# Motor_Surucu_V2.net
KiCad netlist of a schematic drawn in EAGLE
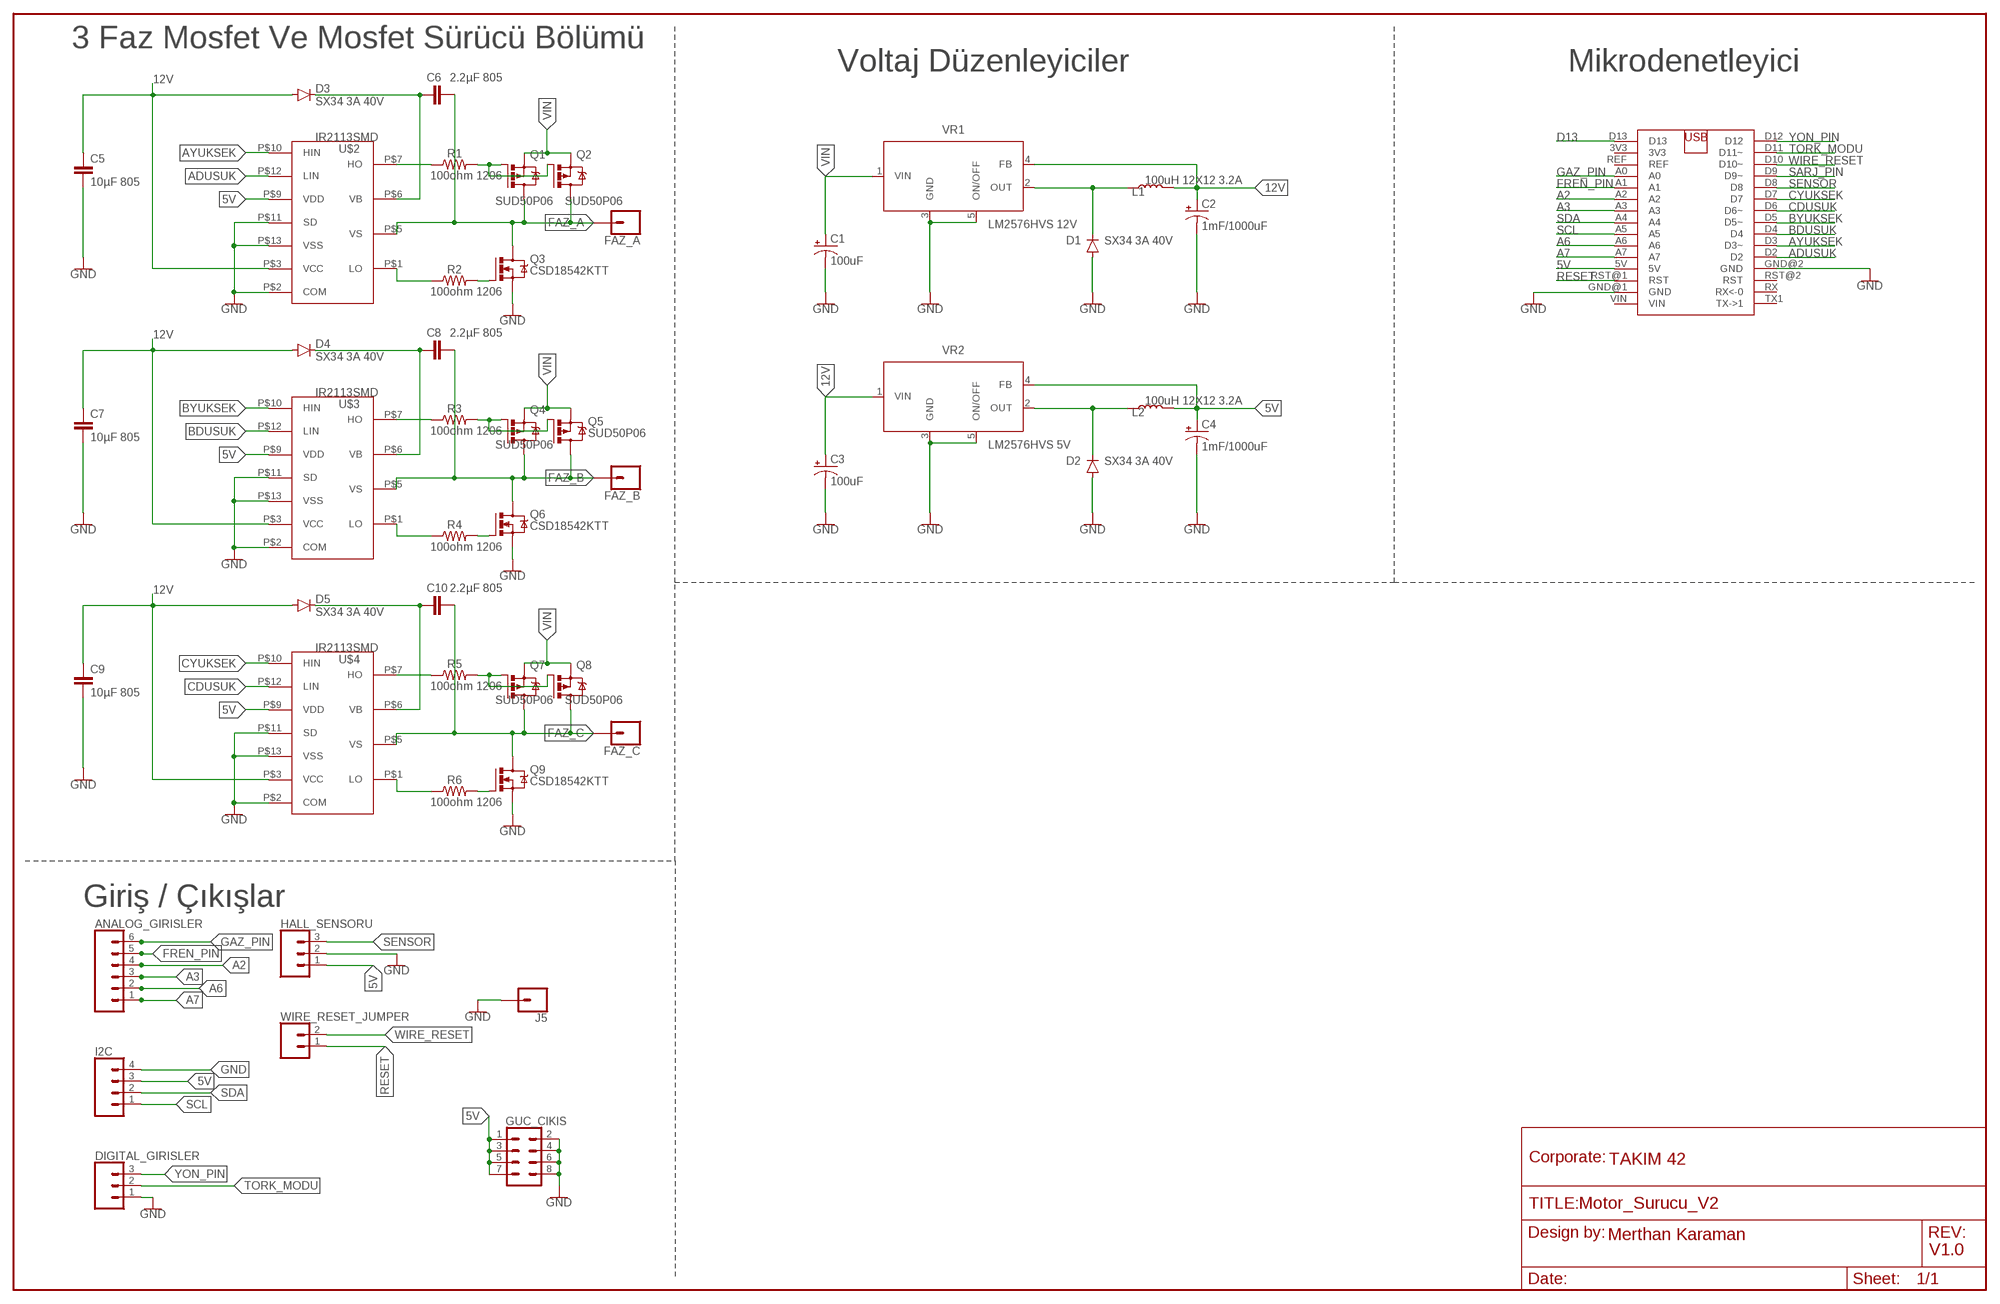
[diagram p0: schematic, sheet 1]

(export (version "E")
  (design (tool "Eeschema 10.0.6"))
  (components
    (comp (ref "ANALOG_GIRISLER")
      (value "CONN_06SILK_FEMALE_PTH")
      (footprint "eagle-import:1X06")
      (libsource (lib "eagle-import") (part "CONN_06SILK_FEMALE_PTH"))
    )
    (comp (ref "C1")
      (value "100uF")
      (footprint "eagle-import:CPOL-RADIAL-2.5MM-6.5MM")
      (libsource (lib "eagle-import") (part "100UF-POLAR-RADIAL-2.5MM-25V-20%"))
    )
    (comp (ref "C2")
      (value "1mF/1000uF")
      (footprint "eagle-import:PANASONIC_G")
      (libsource (lib "eagle-import") (part "560UF-PANASONIC_G-25V-20%"))
    )
    (comp (ref "C3")
      (value "100uF")
      (footprint "eagle-import:CPOL-RADIAL-2.5MM-6.5MM")
      (libsource (lib "eagle-import") (part "100UF-POLAR-RADIAL-2.5MM-25V-20%"))
    )
    (comp (ref "C4")
      (value "1mF/1000uF")
      (footprint "eagle-import:PANASONIC_G")
      (libsource (lib "eagle-import") (part "560UF-PANASONIC_G-25V-20%"))
    )
    (comp (ref "C5")
      (value "10µF 805")
      (footprint "eagle-import:0805")
      (libsource (lib "eagle-import") (part "0.33UF/330NF-0805-50V-10%"))
    )
    (comp (ref "C6")
      (value "2.2µF 805")
      (footprint "eagle-import:0805")
      (libsource (lib "eagle-import") (part "0.33UF/330NF-0805-50V-10%"))
    )
    (comp (ref "C7")
      (value "10µF 805")
      (footprint "eagle-import:0805")
      (libsource (lib "eagle-import") (part "0.33UF/330NF-0805-50V-10%"))
    )
    (comp (ref "C8")
      (value "2.2µF 805")
      (footprint "eagle-import:0805")
      (libsource (lib "eagle-import") (part "0.33UF/330NF-0805-50V-10%"))
    )
    (comp (ref "C9")
      (value "10µF 805")
      (footprint "eagle-import:0805")
      (libsource (lib "eagle-import") (part "0.33UF/330NF-0805-50V-10%"))
    )
    (comp (ref "C10")
      (value "2.2µF 805")
      (footprint "eagle-import:0805")
      (libsource (lib "eagle-import") (part "0.33UF/330NF-0805-50V-10%"))
    )
    (comp (ref "D1")
      (value "SX34 3A 40V")
      (footprint "eagle-import:DO214AC")
      (libsource (lib "eagle-import") (part "DIODE-DO214AC"))
    )
    (comp (ref "D2")
      (value "SX34 3A 40V")
      (footprint "eagle-import:DO214AC")
      (libsource (lib "eagle-import") (part "DIODE-DO214AC"))
    )
    (comp (ref "D3")
      (value "SX34 3A 40V")
      (footprint "eagle-import:DO214AC")
      (libsource (lib "eagle-import") (part "DIODE-DO214AC"))
    )
    (comp (ref "D4")
      (value "SX34 3A 40V")
      (footprint "eagle-import:DO214AC")
      (libsource (lib "eagle-import") (part "DIODE-DO214AC"))
    )
    (comp (ref "D5")
      (value "SX34 3A 40V")
      (footprint "eagle-import:DO214AC")
      (libsource (lib "eagle-import") (part "DIODE-DO214AC"))
    )
    (comp (ref "DIGITAL_GIRISLER")
      (value "CONN_03")
      (footprint "eagle-import:1X03")
      (libsource (lib "eagle-import") (part "CONN_03"))
    )
    (comp (ref "FAZ_A")
      (value "CONN_01SNAP-MALE")
      (footprint "eagle-import:SNAP-MALE")
      (libsource (lib "eagle-import") (part "CONN_01SNAP-MALE"))
    )
    (comp (ref "FAZ_B")
      (value "CONN_01SNAP-MALE")
      (footprint "eagle-import:SNAP-MALE")
      (libsource (lib "eagle-import") (part "CONN_01SNAP-MALE"))
    )
    (comp (ref "FAZ_C")
      (value "CONN_01SNAP-MALE")
      (footprint "eagle-import:SNAP-MALE")
      (libsource (lib "eagle-import") (part "CONN_01SNAP-MALE"))
    )
    (comp (ref "GUC_CIKIS")
      (value "CONN_04X2")
      (footprint "eagle-import:2X4")
      (libsource (lib "eagle-import") (part "CONN_04X2"))
    )
    (comp (ref "HALL_SENSORU")
      (value "CONN_03")
      (footprint "eagle-import:1X03")
      (libsource (lib "eagle-import") (part "CONN_03"))
    )
    (comp (ref "I2C")
      (value "CONN_04")
      (footprint "eagle-import:1X04")
      (libsource (lib "eagle-import") (part "CONN_04"))
    )
    (comp (ref "J5")
      (value "CONN_01SNAP-MALE")
      (footprint "eagle-import:SNAP-MALE")
      (libsource (lib "eagle-import") (part "CONN_01SNAP-MALE"))
    )
    (comp (ref "L1")
      (value "100uH 12X12 3.2A")
      (footprint "eagle-import:INDUCTOR_SDR1307")
      (libsource (lib "eagle-import") (part "INDUCTOR-SDR13-27UH"))
    )
    (comp (ref "L2")
      (value "100uH 12X12 3.2A")
      (footprint "eagle-import:INDUCTOR_SDR1307")
      (libsource (lib "eagle-import") (part "INDUCTOR-SDR13-27UH"))
    )
    (comp (ref "Q1")
      (value "SUD50P06")
      (footprint "eagle-import:TO-252")
      (libsource (lib "eagle-import") (part "SUD50P06"))
    )
    (comp (ref "Q2")
      (value "SUD50P06")
      (footprint "eagle-import:TO-252")
      (libsource (lib "eagle-import") (part "SUD50P06"))
    )
    (comp (ref "Q3")
      (value "CSD18542KTT")
      (footprint "eagle-import:TO263-3")
      (libsource (lib "eagle-import") (part "CSD18542KTT"))
    )
    (comp (ref "Q4")
      (value "SUD50P06")
      (footprint "eagle-import:TO-252")
      (libsource (lib "eagle-import") (part "SUD50P06"))
    )
    (comp (ref "Q5")
      (value "SUD50P06")
      (footprint "eagle-import:TO-252")
      (libsource (lib "eagle-import") (part "SUD50P06"))
    )
    (comp (ref "Q6")
      (value "CSD18542KTT")
      (footprint "eagle-import:TO263-3")
      (libsource (lib "eagle-import") (part "CSD18542KTT"))
    )
    (comp (ref "Q7")
      (value "SUD50P06")
      (footprint "eagle-import:TO-252")
      (libsource (lib "eagle-import") (part "SUD50P06"))
    )
    (comp (ref "Q8")
      (value "SUD50P06")
      (footprint "eagle-import:TO-252")
      (libsource (lib "eagle-import") (part "SUD50P06"))
    )
    (comp (ref "Q9")
      (value "CSD18542KTT")
      (footprint "eagle-import:TO263-3")
      (libsource (lib "eagle-import") (part "CSD18542KTT"))
    )
    (comp (ref "R1")
      (value "100ohm 1206")
      (footprint "eagle-import:1206")
      (libsource (lib "eagle-import") (part "RESISTOR1206"))
    )
    (comp (ref "R2")
      (value "100ohm 1206")
      (footprint "eagle-import:1206")
      (libsource (lib "eagle-import") (part "RESISTOR1206"))
    )
    (comp (ref "R3")
      (value "100ohm 1206")
      (footprint "eagle-import:1206")
      (libsource (lib "eagle-import") (part "RESISTOR1206"))
    )
    (comp (ref "R4")
      (value "100ohm 1206")
      (footprint "eagle-import:1206")
      (libsource (lib "eagle-import") (part "RESISTOR1206"))
    )
    (comp (ref "R5")
      (value "100ohm 1206")
      (footprint "eagle-import:1206")
      (libsource (lib "eagle-import") (part "RESISTOR1206"))
    )
    (comp (ref "R6")
      (value "100ohm 1206")
      (footprint "eagle-import:1206")
      (libsource (lib "eagle-import") (part "RESISTOR1206"))
    )
    (comp (ref "U$1")
      (value "ARDUINO_NANO")
      (footprint "eagle-import:ARDUINO_NANO")
      (libsource (lib "eagle-import") (part "ARDUINO_NANO"))
    )
    (comp (ref "U$2")
      (value "IR2113SMD")
      (footprint "eagle-import:SOIC-14")
      (libsource (lib "eagle-import") (part "IR2113SMD"))
    )
    (comp (ref "U$3")
      (value "IR2113SMD")
      (footprint "eagle-import:SOIC-14")
      (libsource (lib "eagle-import") (part "IR2113SMD"))
    )
    (comp (ref "U$4")
      (value "IR2113SMD")
      (footprint "eagle-import:SOIC-14")
      (libsource (lib "eagle-import") (part "IR2113SMD"))
    )
    (comp (ref "VR1")
      (value "LM2576HVS 12V")
      (footprint "eagle-import:TO170P1435X465-6N")
      (fields (field (name "MANUFACTURER") "TI") (field (name "MPN") "LM2576HVS-5.0/NOPB"))
      (libsource (lib "eagle-import") (part "LM2576HVS-5.0/NOPBTO-263"))
    )
    (comp (ref "VR2")
      (value "LM2576HVS 5V")
      (footprint "eagle-import:TO170P1435X465-6N")
      (fields (field (name "MANUFACTURER") "TI") (field (name "MPN") "LM2576HVS-5.0/NOPB"))
      (libsource (lib "eagle-import") (part "LM2576HVS-5.0/NOPBTO-263"))
    )
    (comp (ref "WIRE_RESET_JUMPER")
      (value "CONN_02")
      (footprint "eagle-import:1X02")
      (libsource (lib "eagle-import") (part "CONN_02"))
    )
  )
  (nets
    (net (code "1") (name "/D13") (class "Default")
      (node (ref "U$1") (pin "D13") (pinfunction "D13_D13") (pintype "bidirectional"))
    )
    (net (code "2") (name "/SARJ_PIN") (class "Default")
      (node (ref "U$1") (pin "D9") (pinfunction "D9~{}_D9") (pintype "bidirectional"))
    )
    (net (code "3") (name "5V") (class "Default")
      (node (ref "C4") (pin "+") (pinfunction "+_+") (pintype "passive"))
      (node (ref "GUC_CIKIS") (pin "1") (pinfunction "1_1") (pintype "passive"))
      (node (ref "GUC_CIKIS") (pin "3") (pinfunction "3_3") (pintype "passive"))
      (node (ref "GUC_CIKIS") (pin "5") (pinfunction "5_5") (pintype "passive"))
      (node (ref "GUC_CIKIS") (pin "7") (pinfunction "7_7") (pintype "passive"))
      (node (ref "HALL_SENSORU") (pin "1") (pinfunction "1_1") (pintype "passive"))
      (node (ref "I2C") (pin "3") (pinfunction "3_3") (pintype "passive"))
      (node (ref "L2") (pin "P$2") (pinfunction "2_P$2") (pintype "passive"))
      (node (ref "U$1") (pin "5V") (pinfunction "5V_5V") (pintype "bidirectional"))
      (node (ref "U$2") (pin "P$9") (pinfunction "VDD_P$9") (pintype "bidirectional"))
      (node (ref "U$3") (pin "P$9") (pinfunction "VDD_P$9") (pintype "bidirectional"))
      (node (ref "U$4") (pin "P$9") (pinfunction "VDD_P$9") (pintype "bidirectional"))
      (node (ref "VR2") (pin "4") (pinfunction "FB_4") (pintype "output"))
    )
    (net (code "4") (name "12V") (class "Default")
      (node (ref "C2") (pin "+") (pinfunction "+_+") (pintype "passive"))
      (node (ref "C3") (pin "1") (pinfunction "+_1") (pintype "passive"))
      (node (ref "C5") (pin "1") (pinfunction "1_1") (pintype "passive"))
      (node (ref "C7") (pin "1") (pinfunction "1_1") (pintype "passive"))
      (node (ref "C9") (pin "1") (pinfunction "1_1") (pintype "passive"))
      (node (ref "D3") (pin "A") (pinfunction "A_A") (pintype "passive"))
      (node (ref "D4") (pin "A") (pinfunction "A_A") (pintype "passive"))
      (node (ref "D5") (pin "A") (pinfunction "A_A") (pintype "passive"))
      (node (ref "L1") (pin "P$2") (pinfunction "2_P$2") (pintype "passive"))
      (node (ref "U$2") (pin "P$3") (pinfunction "VCC_P$3") (pintype "bidirectional"))
      (node (ref "U$3") (pin "P$3") (pinfunction "VCC_P$3") (pintype "bidirectional"))
      (node (ref "U$4") (pin "P$3") (pinfunction "VCC_P$3") (pintype "bidirectional"))
      (node (ref "VR1") (pin "4") (pinfunction "FB_4") (pintype "output"))
      (node (ref "VR2") (pin "1") (pinfunction "VIN_1") (pintype "input"))
    )
    (net (code "5") (name "A2") (class "Default")
      (node (ref "ANALOG_GIRISLER") (pin "4") (pinfunction "4_4") (pintype "passive"))
      (node (ref "U$1") (pin "A2") (pinfunction "A2_A2") (pintype "bidirectional"))
    )
    (net (code "6") (name "A3") (class "Default")
      (node (ref "ANALOG_GIRISLER") (pin "3") (pinfunction "3_3") (pintype "passive"))
      (node (ref "U$1") (pin "A3") (pinfunction "A3_A3") (pintype "bidirectional"))
    )
    (net (code "7") (name "A6") (class "Default")
      (node (ref "ANALOG_GIRISLER") (pin "2") (pinfunction "2_2") (pintype "passive"))
      (node (ref "U$1") (pin "A6") (pinfunction "A6_A6") (pintype "bidirectional"))
    )
    (net (code "8") (name "A7") (class "Default")
      (node (ref "ANALOG_GIRISLER") (pin "1") (pinfunction "1_1") (pintype "passive"))
      (node (ref "U$1") (pin "A7") (pinfunction "A7_A7") (pintype "bidirectional"))
    )
    (net (code "9") (name "ADUSUK") (class "Default")
      (node (ref "U$1") (pin "D2") (pinfunction "D2_D2") (pintype "bidirectional"))
      (node (ref "U$2") (pin "P$12") (pinfunction "LIN_P$12") (pintype "bidirectional"))
    )
    (net (code "10") (name "AYUKSEK") (class "Default")
      (node (ref "U$1") (pin "D3") (pinfunction "D3~{}_D3") (pintype "bidirectional"))
      (node (ref "U$2") (pin "P$10") (pinfunction "HIN_P$10") (pintype "bidirectional"))
    )
    (net (code "11") (name "BDUSUK") (class "Default")
      (node (ref "U$1") (pin "D4") (pinfunction "D4_D4") (pintype "bidirectional"))
      (node (ref "U$3") (pin "P$12") (pinfunction "LIN_P$12") (pintype "bidirectional"))
    )
    (net (code "12") (name "BYUKSEK") (class "Default")
      (node (ref "U$1") (pin "D5") (pinfunction "D5~{}_D5") (pintype "bidirectional"))
      (node (ref "U$3") (pin "P$10") (pinfunction "HIN_P$10") (pintype "bidirectional"))
    )
    (net (code "13") (name "CDUSUK") (class "Default")
      (node (ref "U$1") (pin "D6") (pinfunction "D6~{}_D6") (pintype "bidirectional"))
      (node (ref "U$4") (pin "P$12") (pinfunction "LIN_P$12") (pintype "bidirectional"))
    )
    (net (code "14") (name "CYUKSEK") (class "Default")
      (node (ref "U$1") (pin "D7") (pinfunction "D7_D7") (pintype "bidirectional"))
      (node (ref "U$4") (pin "P$10") (pinfunction "HIN_P$10") (pintype "bidirectional"))
    )
    (net (code "15") (name "FAZ_A") (class "Default")
      (node (ref "C6") (pin "2") (pinfunction "2_2") (pintype "passive"))
      (node (ref "FAZ_A") (pin "2") (pinfunction "1_2") (pintype "passive"))
      (node (ref "Q1") (pin "TAB") (pinfunction "D_TAB") (pintype "passive"))
      (node (ref "Q2") (pin "TAB") (pinfunction "D_TAB") (pintype "passive"))
      (node (ref "Q3") (pin "TAB") (pinfunction "D_TAB") (pintype "passive"))
      (node (ref "U$2") (pin "P$5") (pinfunction "VS_P$5") (pintype "bidirectional"))
    )
    (net (code "16") (name "FAZ_B") (class "Default")
      (node (ref "C8") (pin "2") (pinfunction "2_2") (pintype "passive"))
      (node (ref "FAZ_B") (pin "2") (pinfunction "1_2") (pintype "passive"))
      (node (ref "Q4") (pin "TAB") (pinfunction "D_TAB") (pintype "passive"))
      (node (ref "Q5") (pin "TAB") (pinfunction "D_TAB") (pintype "passive"))
      (node (ref "Q6") (pin "TAB") (pinfunction "D_TAB") (pintype "passive"))
      (node (ref "U$3") (pin "P$5") (pinfunction "VS_P$5") (pintype "bidirectional"))
    )
    (net (code "17") (name "FAZ_C") (class "Default")
      (node (ref "C10") (pin "2") (pinfunction "2_2") (pintype "passive"))
      (node (ref "FAZ_C") (pin "2") (pinfunction "1_2") (pintype "passive"))
      (node (ref "Q7") (pin "TAB") (pinfunction "D_TAB") (pintype "passive"))
      (node (ref "Q8") (pin "TAB") (pinfunction "D_TAB") (pintype "passive"))
      (node (ref "Q9") (pin "TAB") (pinfunction "D_TAB") (pintype "passive"))
      (node (ref "U$4") (pin "P$5") (pinfunction "VS_P$5") (pintype "bidirectional"))
    )
    (net (code "18") (name "FREN_PIN") (class "Default")
      (node (ref "ANALOG_GIRISLER") (pin "5") (pinfunction "5_5") (pintype "passive"))
      (node (ref "U$1") (pin "A1") (pinfunction "A1_A1") (pintype "bidirectional"))
    )
    (net (code "19") (name "GAZ_PIN") (class "Default")
      (node (ref "ANALOG_GIRISLER") (pin "6") (pinfunction "6_6") (pintype "passive"))
      (node (ref "U$1") (pin "A0") (pinfunction "A0_A0") (pintype "bidirectional"))
    )
    (net (code "20") (name "GND") (class "Default")
      (node (ref "C1") (pin "2") (pinfunction "-_2") (pintype "passive"))
      (node (ref "C2") (pin "-") (pinfunction "-_-") (pintype "passive"))
      (node (ref "C3") (pin "2") (pinfunction "-_2") (pintype "passive"))
      (node (ref "C4") (pin "-") (pinfunction "-_-") (pintype "passive"))
      (node (ref "C5") (pin "2") (pinfunction "2_2") (pintype "passive"))
      (node (ref "C7") (pin "2") (pinfunction "2_2") (pintype "passive"))
      (node (ref "C9") (pin "2") (pinfunction "2_2") (pintype "passive"))
      (node (ref "D1") (pin "A") (pinfunction "A_A") (pintype "passive"))
      (node (ref "D2") (pin "A") (pinfunction "A_A") (pintype "passive"))
      (node (ref "DIGITAL_GIRISLER") (pin "1") (pinfunction "1_1") (pintype "passive"))
      (node (ref "GUC_CIKIS") (pin "2") (pinfunction "2_2") (pintype "passive"))
      (node (ref "GUC_CIKIS") (pin "4") (pinfunction "4_4") (pintype "passive"))
      (node (ref "GUC_CIKIS") (pin "6") (pinfunction "6_6") (pintype "passive"))
      (node (ref "GUC_CIKIS") (pin "8") (pinfunction "8_8") (pintype "passive"))
      (node (ref "HALL_SENSORU") (pin "2") (pinfunction "2_2") (pintype "passive"))
      (node (ref "I2C") (pin "4") (pinfunction "4_4") (pintype "passive"))
      (node (ref "J5") (pin "2") (pinfunction "1_2") (pintype "passive"))
      (node (ref "Q3") (pin "3") (pinfunction "S_3") (pintype "passive"))
      (node (ref "Q6") (pin "3") (pinfunction "S_3") (pintype "passive"))
      (node (ref "Q9") (pin "3") (pinfunction "S_3") (pintype "passive"))
      (node (ref "U$1") (pin "GND@1") (pinfunction "GND_GND@1") (pintype "bidirectional"))
      (node (ref "U$1") (pin "GND@2") (pinfunction "GND_GND@2") (pintype "bidirectional"))
      (node (ref "U$2") (pin "P$11") (pinfunction "SD_P$11") (pintype "bidirectional"))
      (node (ref "U$2") (pin "P$13") (pinfunction "VSS_P$13") (pintype "bidirectional"))
      (node (ref "U$2") (pin "P$2") (pinfunction "COM_P$2") (pintype "bidirectional"))
      (node (ref "U$3") (pin "P$11") (pinfunction "SD_P$11") (pintype "bidirectional"))
      (node (ref "U$3") (pin "P$13") (pinfunction "VSS_P$13") (pintype "bidirectional"))
      (node (ref "U$3") (pin "P$2") (pinfunction "COM_P$2") (pintype "bidirectional"))
      (node (ref "U$4") (pin "P$11") (pinfunction "SD_P$11") (pintype "bidirectional"))
      (node (ref "U$4") (pin "P$13") (pinfunction "VSS_P$13") (pintype "bidirectional"))
      (node (ref "U$4") (pin "P$2") (pinfunction "COM_P$2") (pintype "bidirectional"))
      (node (ref "VR1") (pin "3") (pinfunction "GND_3") (pintype "passive"))
      (node (ref "VR1") (pin "5") (pinfunction "ON/OFF_5") (pintype "input"))
      (node (ref "VR2") (pin "3") (pinfunction "GND_3") (pintype "passive"))
      (node (ref "VR2") (pin "5") (pinfunction "ON/OFF_5") (pintype "input"))
    )
    (net (code "21") (name "Net-(L1-1)") (class "Default")
      (node (ref "D1") (pin "C") (pinfunction "C_C") (pintype "passive"))
      (node (ref "L1") (pin "P$1") (pinfunction "1_P$1") (pintype "passive"))
      (node (ref "VR1") (pin "2") (pinfunction "OUT_2") (pintype "output"))
    )
    (net (code "22") (name "Net-(L2-1)") (class "Default")
      (node (ref "D2") (pin "C") (pinfunction "C_C") (pintype "passive"))
      (node (ref "L2") (pin "P$1") (pinfunction "1_P$1") (pintype "passive"))
      (node (ref "VR2") (pin "2") (pinfunction "OUT_2") (pintype "output"))
    )
    (net (code "23") (name "Net-(Q1-G)") (class "Default")
      (node (ref "Q1") (pin "1") (pinfunction "G_1") (pintype "passive"))
      (node (ref "Q2") (pin "1") (pinfunction "G_1") (pintype "passive"))
      (node (ref "R1") (pin "2") (pinfunction "2_2") (pintype "passive"))
    )
    (net (code "24") (name "Net-(Q3-G)") (class "Default")
      (node (ref "Q3") (pin "1") (pinfunction "G_1") (pintype "passive"))
      (node (ref "R2") (pin "2") (pinfunction "2_2") (pintype "passive"))
    )
    (net (code "25") (name "Net-(Q4-G)") (class "Default")
      (node (ref "Q4") (pin "1") (pinfunction "G_1") (pintype "passive"))
      (node (ref "Q5") (pin "1") (pinfunction "G_1") (pintype "passive"))
      (node (ref "R3") (pin "2") (pinfunction "2_2") (pintype "passive"))
    )
    (net (code "26") (name "Net-(Q6-G)") (class "Default")
      (node (ref "Q6") (pin "1") (pinfunction "G_1") (pintype "passive"))
      (node (ref "R4") (pin "2") (pinfunction "2_2") (pintype "passive"))
    )
    (net (code "27") (name "Net-(Q7-G)") (class "Default")
      (node (ref "Q7") (pin "1") (pinfunction "G_1") (pintype "passive"))
      (node (ref "Q8") (pin "1") (pinfunction "G_1") (pintype "passive"))
      (node (ref "R5") (pin "2") (pinfunction "2_2") (pintype "passive"))
    )
    (net (code "28") (name "Net-(Q9-G)") (class "Default")
      (node (ref "Q9") (pin "1") (pinfunction "G_1") (pintype "passive"))
      (node (ref "R6") (pin "2") (pinfunction "2_2") (pintype "passive"))
    )
    (net (code "29") (name "Net-(U$2-HO)") (class "Default")
      (node (ref "R1") (pin "1") (pinfunction "1_1") (pintype "passive"))
      (node (ref "U$2") (pin "P$7") (pinfunction "HO_P$7") (pintype "bidirectional"))
    )
    (net (code "30") (name "Net-(U$2-LO)") (class "Default")
      (node (ref "R2") (pin "1") (pinfunction "1_1") (pintype "passive"))
      (node (ref "U$2") (pin "P$1") (pinfunction "LO_P$1") (pintype "bidirectional"))
    )
    (net (code "31") (name "Net-(U$2-VB)") (class "Default")
      (node (ref "C6") (pin "1") (pinfunction "1_1") (pintype "passive"))
      (node (ref "D3") (pin "C") (pinfunction "C_C") (pintype "passive"))
      (node (ref "U$2") (pin "P$6") (pinfunction "VB_P$6") (pintype "bidirectional"))
    )
    (net (code "32") (name "Net-(U$3-HO)") (class "Default")
      (node (ref "R3") (pin "1") (pinfunction "1_1") (pintype "passive"))
      (node (ref "U$3") (pin "P$7") (pinfunction "HO_P$7") (pintype "bidirectional"))
    )
    (net (code "33") (name "Net-(U$3-LO)") (class "Default")
      (node (ref "R4") (pin "1") (pinfunction "1_1") (pintype "passive"))
      (node (ref "U$3") (pin "P$1") (pinfunction "LO_P$1") (pintype "bidirectional"))
    )
    (net (code "34") (name "Net-(U$3-VB)") (class "Default")
      (node (ref "C8") (pin "1") (pinfunction "1_1") (pintype "passive"))
      (node (ref "D4") (pin "C") (pinfunction "C_C") (pintype "passive"))
      (node (ref "U$3") (pin "P$6") (pinfunction "VB_P$6") (pintype "bidirectional"))
    )
    (net (code "35") (name "Net-(U$4-HO)") (class "Default")
      (node (ref "R5") (pin "1") (pinfunction "1_1") (pintype "passive"))
      (node (ref "U$4") (pin "P$7") (pinfunction "HO_P$7") (pintype "bidirectional"))
    )
    (net (code "36") (name "Net-(U$4-LO)") (class "Default")
      (node (ref "R6") (pin "1") (pinfunction "1_1") (pintype "passive"))
      (node (ref "U$4") (pin "P$1") (pinfunction "LO_P$1") (pintype "bidirectional"))
    )
    (net (code "37") (name "Net-(U$4-VB)") (class "Default")
      (node (ref "C10") (pin "1") (pinfunction "1_1") (pintype "passive"))
      (node (ref "D5") (pin "C") (pinfunction "C_C") (pintype "passive"))
      (node (ref "U$4") (pin "P$6") (pinfunction "VB_P$6") (pintype "bidirectional"))
    )
    (net (code "38") (name "RESET") (class "Default")
      (node (ref "U$1") (pin "RST@1") (pinfunction "RST_RST@1") (pintype "bidirectional"))
      (node (ref "WIRE_RESET_JUMPER") (pin "1") (pinfunction "1_1") (pintype "passive"))
    )
    (net (code "39") (name "SCL") (class "Default")
      (node (ref "I2C") (pin "1") (pinfunction "1_1") (pintype "passive"))
      (node (ref "U$1") (pin "A5") (pinfunction "A5_A5") (pintype "bidirectional"))
    )
    (net (code "40") (name "SDA") (class "Default")
      (node (ref "I2C") (pin "2") (pinfunction "2_2") (pintype "passive"))
      (node (ref "U$1") (pin "A4") (pinfunction "A4_A4") (pintype "bidirectional"))
    )
    (net (code "41") (name "SENSOR") (class "Default")
      (node (ref "HALL_SENSORU") (pin "3") (pinfunction "3_3") (pintype "passive"))
      (node (ref "U$1") (pin "D8") (pinfunction "D8_D8") (pintype "bidirectional"))
    )
    (net (code "42") (name "TORK_MODU") (class "Default")
      (node (ref "DIGITAL_GIRISLER") (pin "2") (pinfunction "2_2") (pintype "passive"))
      (node (ref "U$1") (pin "D11") (pinfunction "D11~{}_D11") (pintype "bidirectional"))
    )
    (net (code "43") (name "VIN") (class "Default")
      (node (ref "C1") (pin "1") (pinfunction "+_1") (pintype "passive"))
      (node (ref "Q1") (pin "3") (pinfunction "S_3") (pintype "passive"))
      (node (ref "Q2") (pin "3") (pinfunction "S_3") (pintype "passive"))
      (node (ref "Q4") (pin "3") (pinfunction "S_3") (pintype "passive"))
      (node (ref "Q5") (pin "3") (pinfunction "S_3") (pintype "passive"))
      (node (ref "Q7") (pin "3") (pinfunction "S_3") (pintype "passive"))
      (node (ref "Q8") (pin "3") (pinfunction "S_3") (pintype "passive"))
      (node (ref "VR1") (pin "1") (pinfunction "VIN_1") (pintype "input"))
    )
    (net (code "44") (name "WIRE_RESET") (class "Default")
      (node (ref "U$1") (pin "D10") (pinfunction "D10~{}_D10") (pintype "bidirectional"))
      (node (ref "WIRE_RESET_JUMPER") (pin "2") (pinfunction "2_2") (pintype "passive"))
    )
    (net (code "45") (name "YON_PIN") (class "Default")
      (node (ref "DIGITAL_GIRISLER") (pin "3") (pinfunction "3_3") (pintype "passive"))
      (node (ref "U$1") (pin "D12") (pinfunction "D12_D12") (pintype "bidirectional"))
    )
    (net (code "46") (name "unconnected-(U$1-Pad3V3)") (class "Default")
      (node (ref "U$1") (pin "3V3") (pinfunction "3V3_3V3") (pintype "bidirectional"))
    )
    (net (code "47") (name "unconnected-(U$1-PadREF)") (class "Default")
      (node (ref "U$1") (pin "REF") (pinfunction "REF_REF") (pintype "bidirectional"))
    )
    (net (code "48") (name "unconnected-(U$1-PadVIN)") (class "Default")
      (node (ref "U$1") (pin "VIN") (pinfunction "VIN_VIN") (pintype "bidirectional"))
    )
    (net (code "49") (name "unconnected-(U$1-RST-PadRST@2)") (class "Default")
      (node (ref "U$1") (pin "RST@2") (pinfunction "RST_RST@2") (pintype "bidirectional"))
    )
    (net (code "50") (name "unconnected-(U$1-RX<-0-PadRX)") (class "Default")
      (node (ref "U$1") (pin "RX") (pinfunction "RX<-0_RX") (pintype "bidirectional"))
    )
    (net (code "51") (name "unconnected-(U$1-TX->1-PadTX1)") (class "Default")
      (node (ref "U$1") (pin "TX1") (pinfunction "TX->1_TX1") (pintype "bidirectional"))
    )
  )
)
